# dual_encoder_i2c.net
KiCad netlist of a schematic drawn in EAGLE
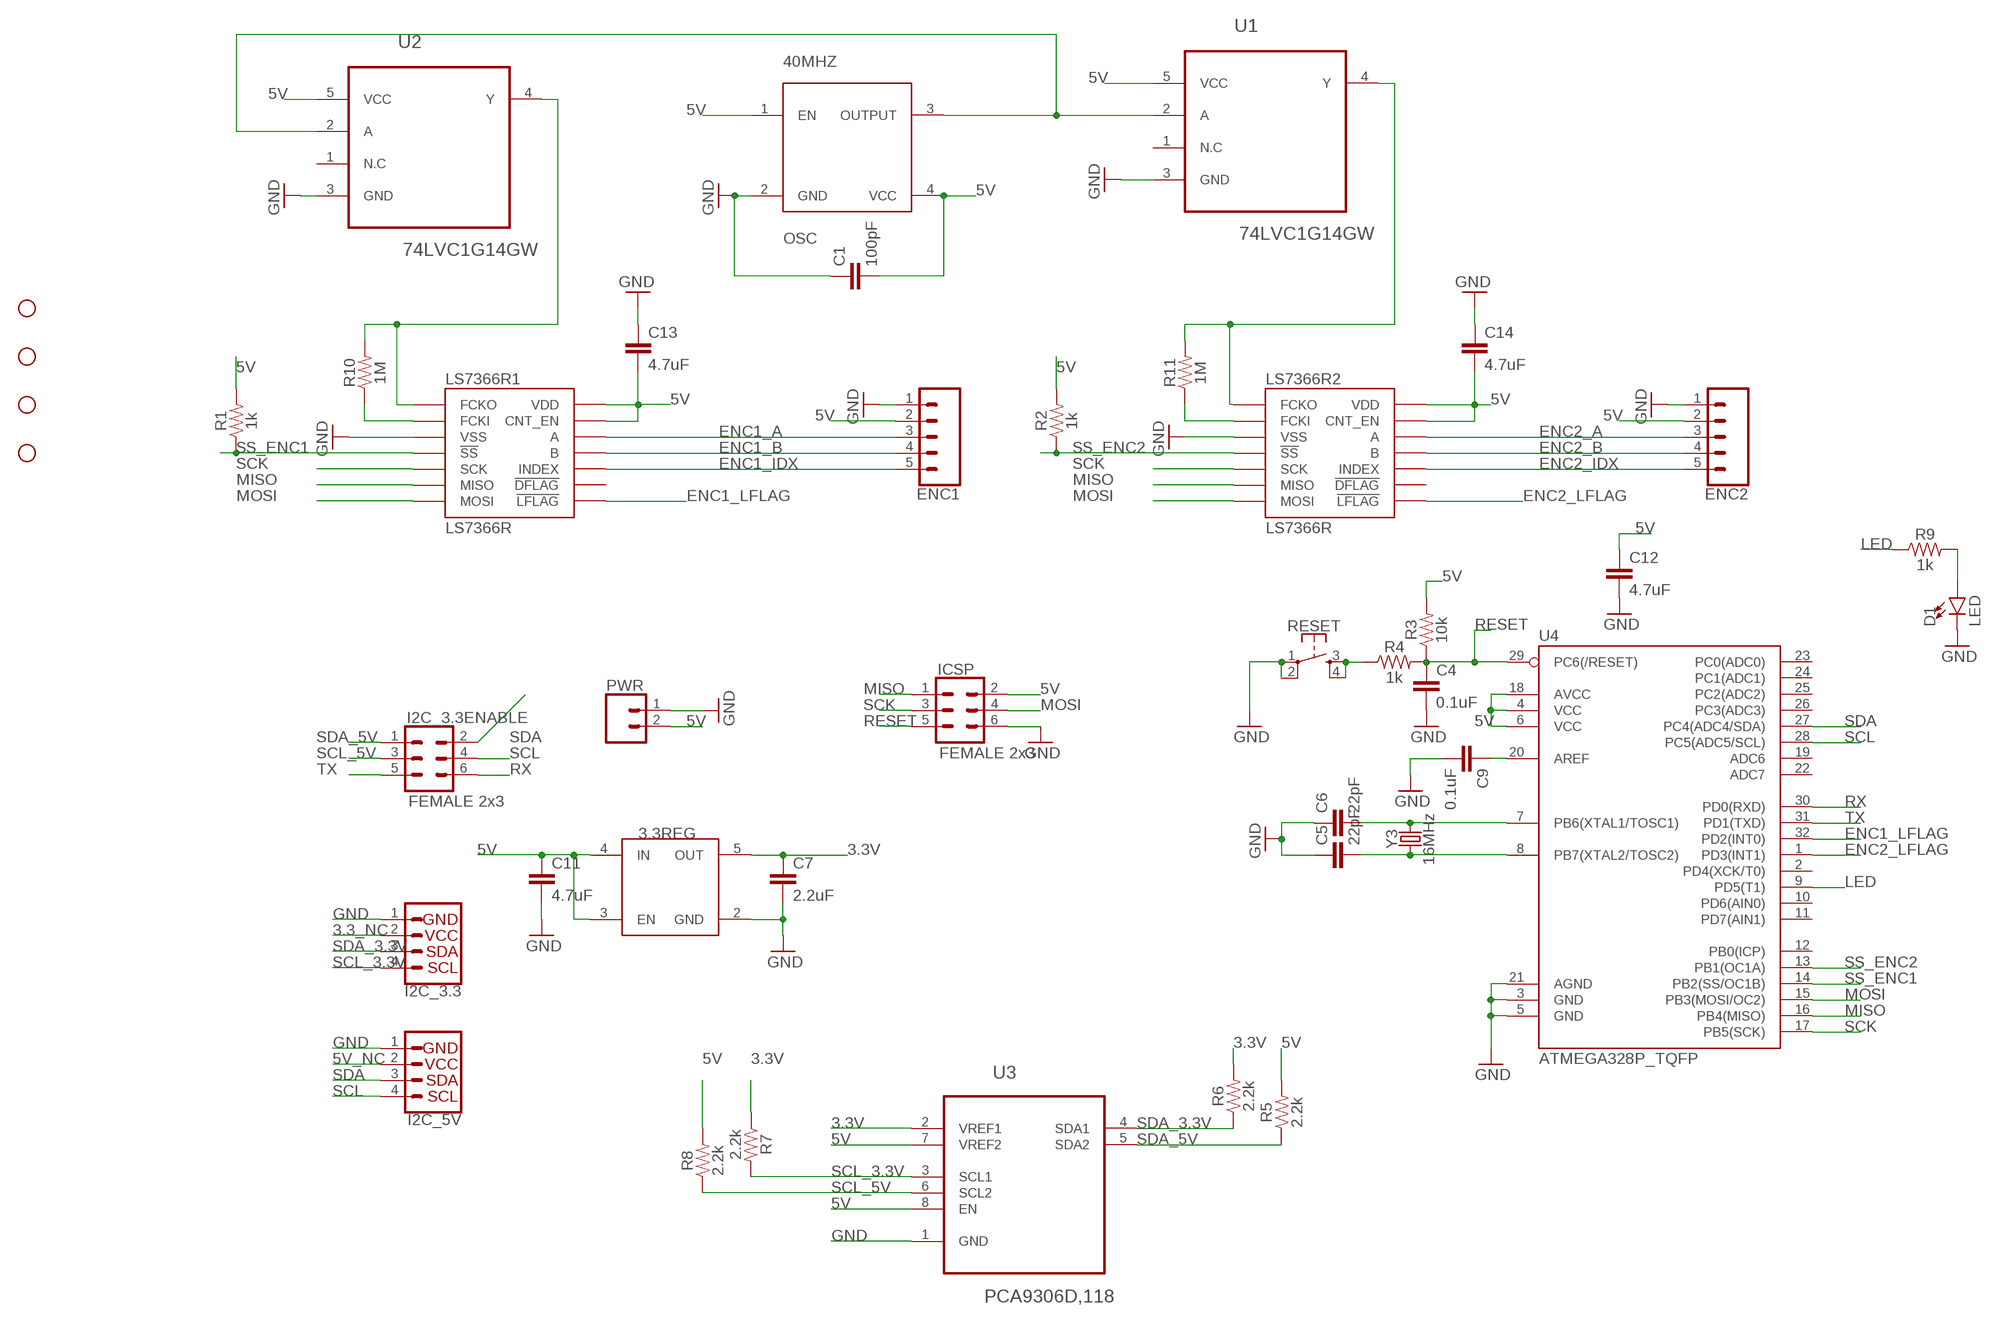
[diagram p0: schematic, sheet 1]

(export (version "E")
  (design (tool "Eeschema 10.0.6"))
  (components
    (comp (ref "3.3REG")
      (value "MIC3490-3.3YM5-TR")
      (footprint "eagle-import:SOT95P285X145-5N")
      (libsource (lib "eagle-import") (part "MIC3490-3.3YM5-TR"))
    )
    (comp (ref "40MHZ")
      (value "OSC")
      (footprint "eagle-import:CB3OSCILLATOR")
      (libsource (lib "eagle-import") (part "OSC"))
    )
    (comp (ref "C1")
      (value "100pF")
      (footprint "eagle-import:0603")
      (libsource (lib "eagle-import") (part "100PF-0603-50V-5%"))
    )
    (comp (ref "C4")
      (value "0.1uF")
      (footprint "eagle-import:0603")
      (libsource (lib "eagle-import") (part "0.1UF-0603-25V-5%"))
    )
    (comp (ref "C5")
      (value "22pF")
      (footprint "eagle-import:0603")
      (libsource (lib "eagle-import") (part "22PF-0603-50V-5%"))
    )
    (comp (ref "C6")
      (value "22pF")
      (footprint "eagle-import:0603")
      (libsource (lib "eagle-import") (part "22PF-0603-50V-5%"))
    )
    (comp (ref "C7")
      (value "2.2uF")
      (footprint "eagle-import:0603")
      (libsource (lib "eagle-import") (part "2.2UF-0603-10V-20%"))
    )
    (comp (ref "C9")
      (value "0.1uF")
      (footprint "eagle-import:0603")
      (libsource (lib "eagle-import") (part "0.1UF-0603-25V-5%"))
    )
    (comp (ref "C11")
      (value "4.7uF")
      (footprint "eagle-import:1206")
      (libsource (lib "eagle-import") (part "4.7UF-1206-16V-(+80/-20%)"))
    )
    (comp (ref "C12")
      (value "4.7uF")
      (footprint "eagle-import:1206")
      (libsource (lib "eagle-import") (part "4.7UF-1206-16V-(+80/-20%)"))
    )
    (comp (ref "C13")
      (value "4.7uF")
      (footprint "eagle-import:1206")
      (libsource (lib "eagle-import") (part "4.7UF-1206-16V-(+80/-20%)"))
    )
    (comp (ref "C14")
      (value "4.7uF")
      (footprint "eagle-import:1206")
      (libsource (lib "eagle-import") (part "4.7UF-1206-16V-(+80/-20%)"))
    )
    (comp (ref "D1")
      (value "LED")
      (footprint "eagle-import:LED-0603")
      (libsource (lib "eagle-import") (part "LED0603"))
    )
    (comp (ref "ENC1")
      (value "CONN_05")
      (footprint "eagle-import:1X05")
      (libsource (lib "eagle-import") (part "CONN_05"))
    )
    (comp (ref "ENC2")
      (value "CONN_05")
      (footprint "eagle-import:1X05")
      (libsource (lib "eagle-import") (part "CONN_05"))
    )
    (comp (ref "H1")
      (value "STAND-OFF")
      (footprint "eagle-import:STAND-OFF")
      (libsource (lib "eagle-import") (part "STAND-OFF"))
    )
    (comp (ref "H2")
      (value "STAND-OFF")
      (footprint "eagle-import:STAND-OFF")
      (libsource (lib "eagle-import") (part "STAND-OFF"))
    )
    (comp (ref "H3")
      (value "STAND-OFF")
      (footprint "eagle-import:STAND-OFF")
      (libsource (lib "eagle-import") (part "STAND-OFF"))
    )
    (comp (ref "H4")
      (value "STAND-OFF")
      (footprint "eagle-import:STAND-OFF")
      (libsource (lib "eagle-import") (part "STAND-OFF"))
    )
    (comp (ref "I2C_3.3")
      (value "QWIIC_CONNECTORJS-1MM")
      (footprint "eagle-import:JST04_1MM_RA")
      (libsource (lib "eagle-import") (part "QWIIC_CONNECTORJS-1MM"))
    )
    (comp (ref "I2C_3.3ENABLE")
      (value "FEMALE 2x3")
      (footprint "eagle-import:2X3")
      (libsource (lib "eagle-import") (part "CONN_03X2FEMALE"))
    )
    (comp (ref "I2C_5V")
      (value "QWIIC_CONNECTORJS-1MM")
      (footprint "eagle-import:JST04_1MM_RA")
      (libsource (lib "eagle-import") (part "QWIIC_CONNECTORJS-1MM"))
    )
    (comp (ref "ICSP")
      (value "FEMALE 2x3")
      (footprint "eagle-import:2X3")
      (libsource (lib "eagle-import") (part "CONN_03X2FEMALE"))
    )
    (comp (ref "LS7366R1")
      (value "LS7366R")
      (footprint "eagle-import:SOIC14")
      (fields (field (name "MF") "LSI"))
      (libsource (lib "eagle-import") (part "LS7366R"))
    )
    (comp (ref "LS7366R2")
      (value "LS7366R")
      (footprint "eagle-import:SOIC14")
      (fields (field (name "MF") "LSI"))
      (libsource (lib "eagle-import") (part "LS7366R"))
    )
    (comp (ref "PWR")
      (value "CONN_02-JST-2MM-SMT")
      (footprint "eagle-import:JST-2-SMD")
      (libsource (lib "eagle-import") (part "CONN_02-JST-2MM-SMT"))
    )
    (comp (ref "R1")
      (value "1k")
      (footprint "eagle-import:0603")
      (libsource (lib "eagle-import") (part "1KOHM-0603-1/10W-1%"))
    )
    (comp (ref "R2")
      (value "1k")
      (footprint "eagle-import:0603")
      (libsource (lib "eagle-import") (part "1KOHM-0603-1/10W-1%"))
    )
    (comp (ref "R3")
      (value "10k")
      (footprint "eagle-import:0603")
      (libsource (lib "eagle-import") (part "10KOHM-0603-1/10W-1%"))
    )
    (comp (ref "R4")
      (value "1k")
      (footprint "eagle-import:0603")
      (libsource (lib "eagle-import") (part "1KOHM-0603-1/10W-1%"))
    )
    (comp (ref "R5")
      (value "2.2k")
      (footprint "eagle-import:0603")
      (libsource (lib "eagle-import") (part "2.2KOHM-0603-1/10W-1%"))
    )
    (comp (ref "R6")
      (value "2.2k")
      (footprint "eagle-import:0603")
      (libsource (lib "eagle-import") (part "2.2KOHM-0603-1/10W-1%"))
    )
    (comp (ref "R7")
      (value "2.2k")
      (footprint "eagle-import:0603")
      (libsource (lib "eagle-import") (part "2.2KOHM-0603-1/10W-1%"))
    )
    (comp (ref "R8")
      (value "2.2k")
      (footprint "eagle-import:0603")
      (libsource (lib "eagle-import") (part "2.2KOHM-0603-1/10W-1%"))
    )
    (comp (ref "R9")
      (value "1k")
      (footprint "eagle-import:0603")
      (libsource (lib "eagle-import") (part "1KOHM-0603-1/10W-1%"))
    )
    (comp (ref "R10")
      (value "1M")
      (footprint "eagle-import:0603")
      (libsource (lib "eagle-import") (part "1MOHM-0603-1/4W-5%"))
    )
    (comp (ref "R11")
      (value "1M")
      (footprint "eagle-import:0603")
      (libsource (lib "eagle-import") (part "1MOHM-0603-1/4W-5%"))
    )
    (comp (ref "RESET")
      (value "MOMENTARY-SWITCH-SPST-2-SMD-5.2MM")
      (footprint "eagle-import:TACTILE_SWITCH_SMD_5.2MM")
      (libsource (lib "eagle-import") (part "MOMENTARY-SWITCH-SPST-2-SMD-5.2MM"))
    )
    (comp (ref "U1")
      (value "74LVC1G14GW")
      (footprint "eagle-import:SOT65P210X110-5N")
      (fields (field (name "MF") "NXP Semiconductors"))
      (libsource (lib "eagle-import") (part "74LVC1G14GW"))
    )
    (comp (ref "U2")
      (value "74LVC1G14GW")
      (footprint "eagle-import:SOT65P210X110-5N")
      (fields (field (name "MF") "NXP Semiconductors"))
      (libsource (lib "eagle-import") (part "74LVC1G14GW"))
    )
    (comp (ref "U3")
      (value "PCA9306D,118")
      (footprint "eagle-import:SOIC127P600X175-8N")
      (fields (field (name "MF") "NXP USA"))
      (libsource (lib "eagle-import") (part "PCA9306D,118"))
    )
    (comp (ref "U4")
      (value "ATMEGA328P_TQFP")
      (footprint "eagle-import:TQFP32-08")
      (libsource (lib "eagle-import") (part "ATMEGA328P_TQFP"))
    )
    (comp (ref "Y3")
      (value "16MHz")
      (footprint "eagle-import:CRYSTAL-SMD-5X3.2-4PAD")
      (libsource (lib "eagle-import") (part "CRYSTAL-16MHZSMD-5X3.2"))
    )
  )
  (nets
    (net (code "1") (name "/3.3V") (class "Default")
      (node (ref "3.3REG") (pin "5") (pinfunction "OUT_5") (pintype "output"))
      (node (ref "C7") (pin "1") (pinfunction "1_1") (pintype "passive"))
      (node (ref "R6") (pin "2") (pinfunction "2_2") (pintype "passive"))
      (node (ref "R7") (pin "1") (pinfunction "1_1") (pintype "passive"))
      (node (ref "U3") (pin "2") (pinfunction "VREF1_2") (pintype "power_in"))
    )
    (net (code "2") (name "/3.3_NC") (class "Default")
      (node (ref "I2C_3.3") (pin "2") (pinfunction "2_2") (pintype "power_in"))
    )
    (net (code "3") (name "/5V") (class "Default")
      (node (ref "3.3REG") (pin "3") (pinfunction "EN_3") (pintype "input"))
      (node (ref "3.3REG") (pin "4") (pinfunction "IN_4") (pintype "input"))
      (node (ref "40MHZ") (pin "1") (pinfunction "EN_1") (pintype "input"))
      (node (ref "40MHZ") (pin "4") (pinfunction "VCC_4") (pintype "input"))
      (node (ref "C1") (pin "2") (pinfunction "2_2") (pintype "passive"))
      (node (ref "C11") (pin "1") (pinfunction "1_1") (pintype "passive"))
      (node (ref "C12") (pin "1") (pinfunction "1_1") (pintype "passive"))
      (node (ref "C13") (pin "2") (pinfunction "2_2") (pintype "passive"))
      (node (ref "C14") (pin "2") (pinfunction "2_2") (pintype "passive"))
      (node (ref "ENC1") (pin "2") (pinfunction "2_2") (pintype "passive"))
      (node (ref "ENC2") (pin "2") (pinfunction "2_2") (pintype "passive"))
      (node (ref "ICSP") (pin "2") (pinfunction "2_2") (pintype "bidirectional"))
      (node (ref "LS7366R1") (pin "13") (pinfunction "CNT_EN_13") (pintype "bidirectional"))
      (node (ref "LS7366R1") (pin "14") (pinfunction "VDD_14") (pintype "bidirectional"))
      (node (ref "LS7366R2") (pin "13") (pinfunction "CNT_EN_13") (pintype "bidirectional"))
      (node (ref "LS7366R2") (pin "14") (pinfunction "VDD_14") (pintype "bidirectional"))
      (node (ref "PWR") (pin "2") (pinfunction "1_2") (pintype "passive"))
      (node (ref "R1") (pin "2") (pinfunction "2_2") (pintype "passive"))
      (node (ref "R2") (pin "2") (pinfunction "2_2") (pintype "passive"))
      (node (ref "R3") (pin "2") (pinfunction "2_2") (pintype "passive"))
      (node (ref "R5") (pin "2") (pinfunction "2_2") (pintype "passive"))
      (node (ref "R8") (pin "2") (pinfunction "2_2") (pintype "passive"))
      (node (ref "U1") (pin "5") (pinfunction "VCC_5") (pintype "power_in"))
      (node (ref "U2") (pin "5") (pinfunction "VCC_5") (pintype "power_in"))
      (node (ref "U3") (pin "7") (pinfunction "VREF2_7") (pintype "power_in"))
      (node (ref "U3") (pin "8") (pinfunction "EN_8") (pintype "input"))
      (node (ref "U4") (pin "18") (pinfunction "AVCC_18") (pintype "bidirectional"))
      (node (ref "U4") (pin "4") (pinfunction "VCC_4") (pintype "bidirectional"))
      (node (ref "U4") (pin "6") (pinfunction "VCC_6") (pintype "bidirectional"))
    )
    (net (code "4") (name "/5V_NC") (class "Default")
      (node (ref "I2C_5V") (pin "2") (pinfunction "2_2") (pintype "power_in"))
    )
    (net (code "5") (name "/ENC1_A") (class "Default")
      (node (ref "ENC1") (pin "3") (pinfunction "3_3") (pintype "passive"))
      (node (ref "LS7366R1") (pin "12") (pinfunction "A_12") (pintype "bidirectional"))
    )
    (net (code "6") (name "/ENC1_B") (class "Default")
      (node (ref "ENC1") (pin "4") (pinfunction "4_4") (pintype "passive"))
      (node (ref "LS7366R1") (pin "11") (pinfunction "B_11") (pintype "bidirectional"))
    )
    (net (code "7") (name "/ENC1_IDX") (class "Default")
      (node (ref "ENC1") (pin "5") (pinfunction "5_5") (pintype "passive"))
      (node (ref "LS7366R1") (pin "10") (pinfunction "INDEX_10") (pintype "bidirectional"))
    )
    (net (code "8") (name "/ENC1_LFLAG") (class "Default")
      (node (ref "LS7366R1") (pin "8") (pinfunction "~{LFLAG}_8") (pintype "bidirectional"))
      (node (ref "U4") (pin "32") (pinfunction "PD2(INT0)_32") (pintype "bidirectional"))
    )
    (net (code "9") (name "/ENC2_A") (class "Default")
      (node (ref "ENC2") (pin "3") (pinfunction "3_3") (pintype "passive"))
      (node (ref "LS7366R2") (pin "12") (pinfunction "A_12") (pintype "bidirectional"))
    )
    (net (code "10") (name "/ENC2_B") (class "Default")
      (node (ref "ENC2") (pin "4") (pinfunction "4_4") (pintype "passive"))
      (node (ref "LS7366R2") (pin "11") (pinfunction "B_11") (pintype "bidirectional"))
    )
    (net (code "11") (name "/ENC2_IDX") (class "Default")
      (node (ref "ENC2") (pin "5") (pinfunction "5_5") (pintype "passive"))
      (node (ref "LS7366R2") (pin "10") (pinfunction "INDEX_10") (pintype "bidirectional"))
    )
    (net (code "12") (name "/ENC2_LFLAG") (class "Default")
      (node (ref "LS7366R2") (pin "8") (pinfunction "~{LFLAG}_8") (pintype "bidirectional"))
      (node (ref "U4") (pin "1") (pinfunction "PD3(INT1)_1") (pintype "bidirectional"))
    )
    (net (code "13") (name "/LED") (class "Default")
      (node (ref "R9") (pin "1") (pinfunction "1_1") (pintype "passive"))
      (node (ref "U4") (pin "9") (pinfunction "PD5(T1)_9") (pintype "bidirectional"))
    )
    (net (code "14") (name "/MISO") (class "Default")
      (node (ref "ICSP") (pin "1") (pinfunction "1_1") (pintype "bidirectional"))
      (node (ref "LS7366R1") (pin "6") (pinfunction "MISO_6") (pintype "bidirectional"))
      (node (ref "LS7366R2") (pin "6") (pinfunction "MISO_6") (pintype "bidirectional"))
      (node (ref "U4") (pin "16") (pinfunction "PB4(MISO)_16") (pintype "bidirectional"))
    )
    (net (code "15") (name "/MOSI") (class "Default")
      (node (ref "ICSP") (pin "4") (pinfunction "4_4") (pintype "bidirectional"))
      (node (ref "LS7366R1") (pin "7") (pinfunction "MOSI_7") (pintype "bidirectional"))
      (node (ref "LS7366R2") (pin "7") (pinfunction "MOSI_7") (pintype "bidirectional"))
      (node (ref "U4") (pin "15") (pinfunction "PB3(MOSI/OC2)_15") (pintype "bidirectional"))
    )
    (net (code "16") (name "/RESET") (class "Default")
      (node (ref "C4") (pin "1") (pinfunction "1_1") (pintype "passive"))
      (node (ref "ICSP") (pin "5") (pinfunction "5_5") (pintype "bidirectional"))
      (node (ref "R3") (pin "1") (pinfunction "1_1") (pintype "passive"))
      (node (ref "R4") (pin "2") (pinfunction "2_2") (pintype "passive"))
      (node (ref "U4") (pin "29") (pinfunction "PC6(/RESET)_29") (pintype "bidirectional"))
    )
    (net (code "17") (name "/RX") (class "Default")
      (node (ref "I2C_3.3ENABLE") (pin "6") (pinfunction "6_6") (pintype "bidirectional"))
      (node (ref "U4") (pin "30") (pinfunction "PD0(RXD)_30") (pintype "bidirectional"))
    )
    (net (code "18") (name "/SCK") (class "Default")
      (node (ref "ICSP") (pin "3") (pinfunction "3_3") (pintype "bidirectional"))
      (node (ref "LS7366R1") (pin "5") (pinfunction "SCK_5") (pintype "bidirectional"))
      (node (ref "LS7366R2") (pin "5") (pinfunction "SCK_5") (pintype "bidirectional"))
      (node (ref "U4") (pin "17") (pinfunction "PB5(SCK)_17") (pintype "bidirectional"))
    )
    (net (code "19") (name "/SCL") (class "Default")
      (node (ref "I2C_3.3ENABLE") (pin "4") (pinfunction "4_4") (pintype "bidirectional"))
      (node (ref "I2C_5V") (pin "4") (pinfunction "4_4") (pintype "passive"))
      (node (ref "U4") (pin "28") (pinfunction "PC5(ADC5/SCL)_28") (pintype "bidirectional"))
    )
    (net (code "20") (name "/SCL_3.3V") (class "Default")
      (node (ref "I2C_3.3") (pin "4") (pinfunction "4_4") (pintype "passive"))
      (node (ref "R7") (pin "2") (pinfunction "2_2") (pintype "passive"))
      (node (ref "U3") (pin "3") (pinfunction "SCL1_3") (pintype "input"))
    )
    (net (code "21") (name "/SCL_5V") (class "Default")
      (node (ref "I2C_3.3ENABLE") (pin "3") (pinfunction "3_3") (pintype "bidirectional"))
      (node (ref "R8") (pin "1") (pinfunction "1_1") (pintype "passive"))
      (node (ref "U3") (pin "6") (pinfunction "SCL2_6") (pintype "input"))
    )
    (net (code "22") (name "/SDA") (class "Default")
      (node (ref "I2C_3.3ENABLE") (pin "2") (pinfunction "2_2") (pintype "bidirectional"))
      (node (ref "I2C_5V") (pin "3") (pinfunction "3_3") (pintype "passive"))
      (node (ref "U4") (pin "27") (pinfunction "PC4(ADC4/SDA)_27") (pintype "bidirectional"))
    )
    (net (code "23") (name "/SDA_3.3V") (class "Default")
      (node (ref "I2C_3.3") (pin "3") (pinfunction "3_3") (pintype "passive"))
      (node (ref "R6") (pin "1") (pinfunction "1_1") (pintype "passive"))
      (node (ref "U3") (pin "4") (pinfunction "SDA1_4") (pintype "bidirectional"))
    )
    (net (code "24") (name "/SDA_5V") (class "Default")
      (node (ref "I2C_3.3ENABLE") (pin "1") (pinfunction "1_1") (pintype "bidirectional"))
      (node (ref "R5") (pin "1") (pinfunction "1_1") (pintype "passive"))
      (node (ref "U3") (pin "5") (pinfunction "SDA2_5") (pintype "bidirectional"))
    )
    (net (code "25") (name "/SS_ENC1") (class "Default")
      (node (ref "LS7366R1") (pin "4") (pinfunction "~{SS}_4") (pintype "bidirectional"))
      (node (ref "R1") (pin "1") (pinfunction "1_1") (pintype "passive"))
      (node (ref "U4") (pin "14") (pinfunction "PB2(SS/OC1B)_14") (pintype "bidirectional"))
    )
    (net (code "26") (name "/SS_ENC2") (class "Default")
      (node (ref "LS7366R2") (pin "4") (pinfunction "~{SS}_4") (pintype "bidirectional"))
      (node (ref "R2") (pin "1") (pinfunction "1_1") (pintype "passive"))
      (node (ref "U4") (pin "13") (pinfunction "PB1(OC1A)_13") (pintype "bidirectional"))
    )
    (net (code "27") (name "/TX") (class "Default")
      (node (ref "I2C_3.3ENABLE") (pin "5") (pinfunction "5_5") (pintype "bidirectional"))
      (node (ref "U4") (pin "31") (pinfunction "PD1(TXD)_31") (pintype "bidirectional"))
    )
    (net (code "28") (name "GND") (class "Default")
      (node (ref "3.3REG") (pin "2") (pinfunction "GND_2") (pintype "bidirectional"))
      (node (ref "40MHZ") (pin "2") (pinfunction "GND_2") (pintype "input"))
      (node (ref "C1") (pin "1") (pinfunction "1_1") (pintype "passive"))
      (node (ref "C11") (pin "2") (pinfunction "2_2") (pintype "passive"))
      (node (ref "C12") (pin "2") (pinfunction "2_2") (pintype "passive"))
      (node (ref "C13") (pin "1") (pinfunction "1_1") (pintype "passive"))
      (node (ref "C14") (pin "1") (pinfunction "1_1") (pintype "passive"))
      (node (ref "C4") (pin "2") (pinfunction "2_2") (pintype "passive"))
      (node (ref "C5") (pin "1") (pinfunction "1_1") (pintype "passive"))
      (node (ref "C6") (pin "1") (pinfunction "1_1") (pintype "passive"))
      (node (ref "C7") (pin "2") (pinfunction "2_2") (pintype "passive"))
      (node (ref "C9") (pin "2") (pinfunction "2_2") (pintype "passive"))
      (node (ref "D1") (pin "C") (pinfunction "C_C") (pintype "passive"))
      (node (ref "ENC1") (pin "1") (pinfunction "1_1") (pintype "passive"))
      (node (ref "ENC2") (pin "1") (pinfunction "1_1") (pintype "passive"))
      (node (ref "I2C_3.3") (pin "1") (pinfunction "1_1") (pintype "power_in"))
      (node (ref "I2C_5V") (pin "1") (pinfunction "1_1") (pintype "power_in"))
      (node (ref "ICSP") (pin "6") (pinfunction "6_6") (pintype "bidirectional"))
      (node (ref "LS7366R1") (pin "3") (pinfunction "VSS_3") (pintype "bidirectional"))
      (node (ref "LS7366R2") (pin "3") (pinfunction "VSS_3") (pintype "bidirectional"))
      (node (ref "PWR") (pin "1") (pinfunction "2_1") (pintype "passive"))
      (node (ref "RESET") (pin "1") (pinfunction "1_1") (pintype "passive"))
      (node (ref "RESET") (pin "2") (pinfunction "2_2") (pintype "passive"))
      (node (ref "U1") (pin "3") (pinfunction "GND_3") (pintype "passive"))
      (node (ref "U2") (pin "3") (pinfunction "GND_3") (pintype "passive"))
      (node (ref "U3") (pin "1") (pinfunction "GND_1") (pintype "passive"))
      (node (ref "U4") (pin "21") (pinfunction "AGND_21") (pintype "bidirectional"))
      (node (ref "U4") (pin "3") (pinfunction "GND_3") (pintype "bidirectional"))
      (node (ref "U4") (pin "5") (pinfunction "GND_5") (pintype "bidirectional"))
    )
    (net (code "29") (name "Net-(40MHZ-OUTPUT)") (class "Default")
      (node (ref "40MHZ") (pin "3") (pinfunction "OUTPUT_3") (pintype "output"))
      (node (ref "U1") (pin "2") (pinfunction "A_2") (pintype "input"))
      (node (ref "U2") (pin "2") (pinfunction "A_2") (pintype "input"))
    )
    (net (code "30") (name "Net-(D1-PadA)") (class "Default")
      (node (ref "D1") (pin "A") (pinfunction "A_A") (pintype "passive"))
      (node (ref "R9") (pin "2") (pinfunction "2_2") (pintype "passive"))
    )
    (net (code "31") (name "Net-(LS7366R1-FCKI)") (class "Default")
      (node (ref "LS7366R1") (pin "2") (pinfunction "FCKI_2") (pintype "bidirectional"))
      (node (ref "R10") (pin "1") (pinfunction "1_1") (pintype "passive"))
    )
    (net (code "32") (name "Net-(LS7366R1-FCKO)") (class "Default")
      (node (ref "LS7366R1") (pin "1") (pinfunction "FCKO_1") (pintype "bidirectional"))
      (node (ref "R10") (pin "2") (pinfunction "2_2") (pintype "passive"))
      (node (ref "U2") (pin "4") (pinfunction "Y_4") (pintype "output"))
    )
    (net (code "33") (name "Net-(LS7366R2-FCKI)") (class "Default")
      (node (ref "LS7366R2") (pin "2") (pinfunction "FCKI_2") (pintype "bidirectional"))
      (node (ref "R11") (pin "1") (pinfunction "1_1") (pintype "passive"))
    )
    (net (code "34") (name "Net-(LS7366R2-FCKO)") (class "Default")
      (node (ref "LS7366R2") (pin "1") (pinfunction "FCKO_1") (pintype "bidirectional"))
      (node (ref "R11") (pin "2") (pinfunction "2_2") (pintype "passive"))
      (node (ref "U1") (pin "4") (pinfunction "Y_4") (pintype "output"))
    )
    (net (code "35") (name "Net-(R4-Pad1)") (class "Default")
      (node (ref "R4") (pin "1") (pinfunction "1_1") (pintype "passive"))
      (node (ref "RESET") (pin "3") (pinfunction "3_3") (pintype "passive"))
      (node (ref "RESET") (pin "4") (pinfunction "4_4") (pintype "passive"))
    )
    (net (code "36") (name "Net-(U4-AREF)") (class "Default")
      (node (ref "C9") (pin "1") (pinfunction "1_1") (pintype "passive"))
      (node (ref "U4") (pin "20") (pinfunction "AREF_20") (pintype "bidirectional"))
    )
    (net (code "37") (name "Net-(U4-PB6(XTAL1{slash}TOSC1))") (class "Default")
      (node (ref "C6") (pin "2") (pinfunction "2_2") (pintype "passive"))
      (node (ref "U4") (pin "7") (pinfunction "PB6(XTAL1/TOSC1)_7") (pintype "bidirectional"))
      (node (ref "Y3") (pin "3") (pinfunction "2_3") (pintype "passive"))
    )
    (net (code "38") (name "Net-(U4-PB7(XTAL2{slash}TOSC2))") (class "Default")
      (node (ref "C5") (pin "2") (pinfunction "2_2") (pintype "passive"))
      (node (ref "U4") (pin "8") (pinfunction "PB7(XTAL2/TOSC2)_8") (pintype "bidirectional"))
      (node (ref "Y3") (pin "1") (pinfunction "1_1") (pintype "passive"))
    )
    (net (code "39") (name "unconnected-(LS7366R1-~{DFLAG}-Pad9)") (class "Default")
      (node (ref "LS7366R1") (pin "9") (pinfunction "~{DFLAG}_9") (pintype "bidirectional"))
    )
    (net (code "40") (name "unconnected-(LS7366R2-~{DFLAG}-Pad9)") (class "Default")
      (node (ref "LS7366R2") (pin "9") (pinfunction "~{DFLAG}_9") (pintype "bidirectional"))
    )
    (net (code "41") (name "unconnected-(U1-N.C-Pad1)") (class "Default")
      (node (ref "U1") (pin "1") (pinfunction "N.C_1") (pintype "no_connect"))
    )
    (net (code "42") (name "unconnected-(U2-N.C-Pad1)") (class "Default")
      (node (ref "U2") (pin "1") (pinfunction "N.C_1") (pintype "no_connect"))
    )
    (net (code "43") (name "unconnected-(U4-ADC6-Pad19)") (class "Default")
      (node (ref "U4") (pin "19") (pinfunction "ADC6_19") (pintype "bidirectional"))
    )
    (net (code "44") (name "unconnected-(U4-ADC7-Pad22)") (class "Default")
      (node (ref "U4") (pin "22") (pinfunction "ADC7_22") (pintype "bidirectional"))
    )
    (net (code "45") (name "unconnected-(U4-PB0(ICP)-Pad12)") (class "Default")
      (node (ref "U4") (pin "12") (pinfunction "PB0(ICP)_12") (pintype "bidirectional"))
    )
    (net (code "46") (name "unconnected-(U4-PC0(ADC0)-Pad23)") (class "Default")
      (node (ref "U4") (pin "23") (pinfunction "PC0(ADC0)_23") (pintype "bidirectional"))
    )
    (net (code "47") (name "unconnected-(U4-PC1(ADC1)-Pad24)") (class "Default")
      (node (ref "U4") (pin "24") (pinfunction "PC1(ADC1)_24") (pintype "bidirectional"))
    )
    (net (code "48") (name "unconnected-(U4-PC2(ADC2)-Pad25)") (class "Default")
      (node (ref "U4") (pin "25") (pinfunction "PC2(ADC2)_25") (pintype "bidirectional"))
    )
    (net (code "49") (name "unconnected-(U4-PC3(ADC3)-Pad26)") (class "Default")
      (node (ref "U4") (pin "26") (pinfunction "PC3(ADC3)_26") (pintype "bidirectional"))
    )
    (net (code "50") (name "unconnected-(U4-PD4(XCK{slash}T0)-Pad2)") (class "Default")
      (node (ref "U4") (pin "2") (pinfunction "PD4(XCK/T0)_2") (pintype "bidirectional"))
    )
    (net (code "51") (name "unconnected-(U4-PD6(AIN0)-Pad10)") (class "Default")
      (node (ref "U4") (pin "10") (pinfunction "PD6(AIN0)_10") (pintype "bidirectional"))
    )
    (net (code "52") (name "unconnected-(U4-PD7(AIN1)-Pad11)") (class "Default")
      (node (ref "U4") (pin "11") (pinfunction "PD7(AIN1)_11") (pintype "bidirectional"))
    )
  )
)
